# LEDs.net
KiCad netlist of a schematic drawn in Altium Designer
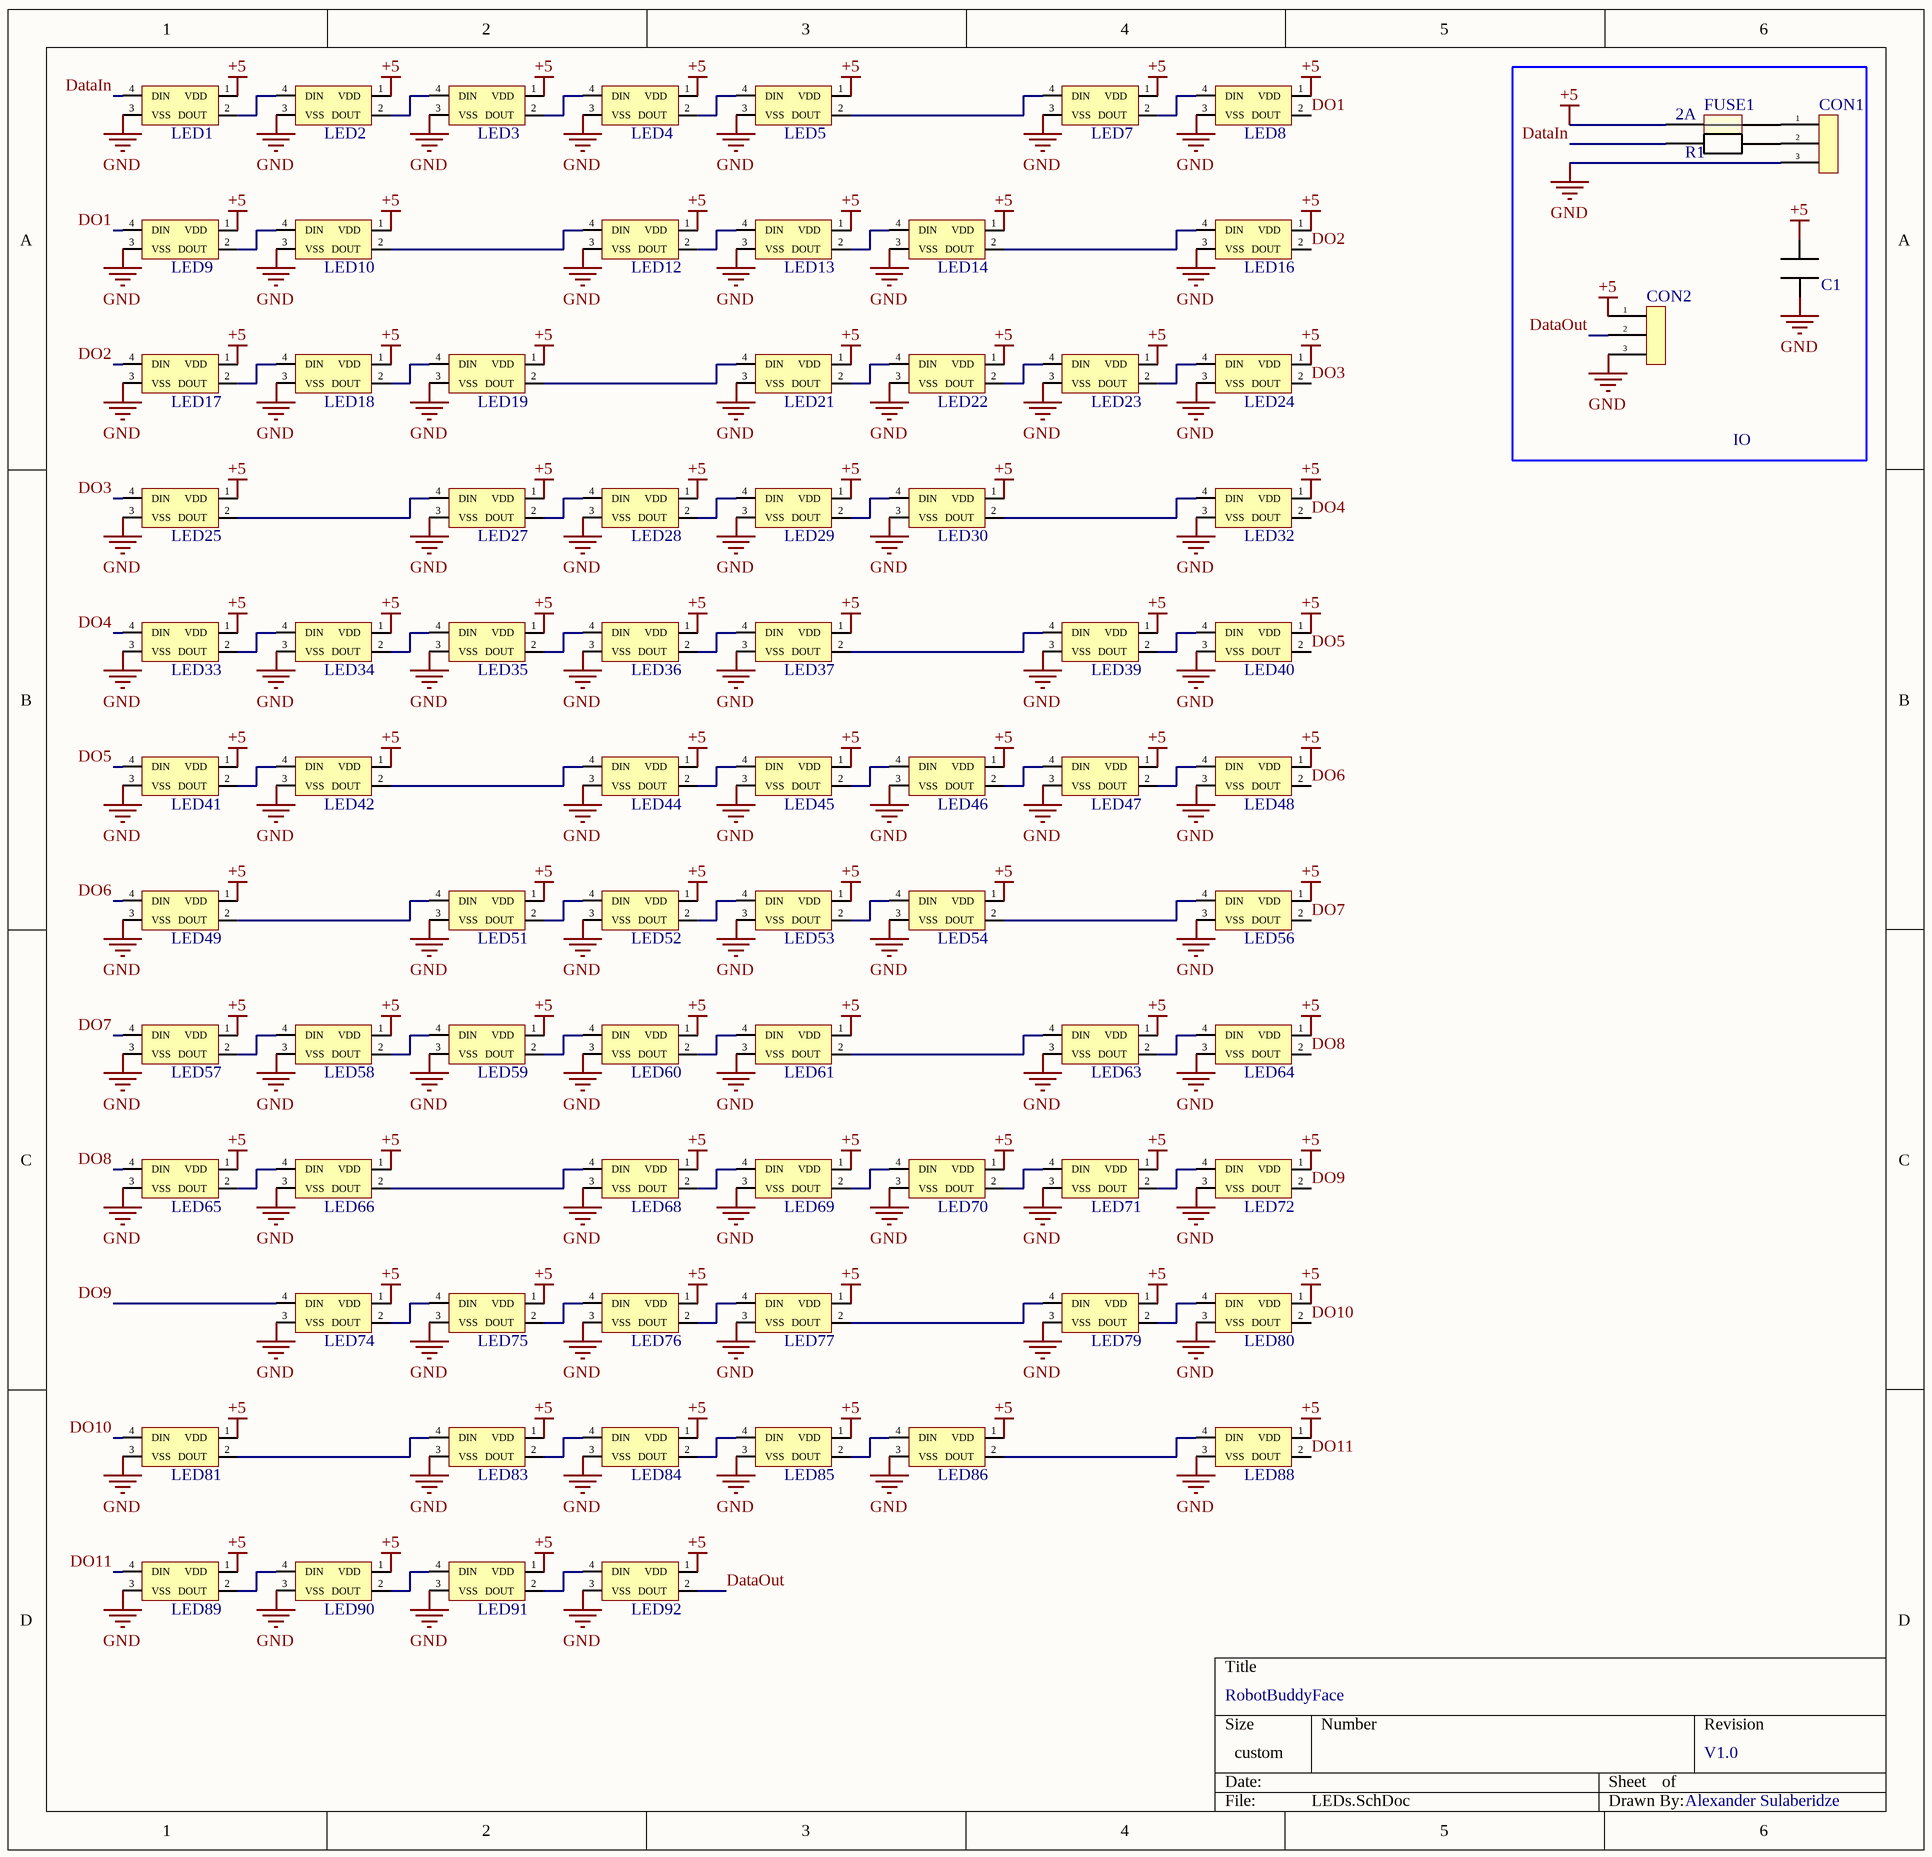
[diagram p0: LEDs.SchDoc]

(export (version "E")
  (design (tool "Eeschema 10.0.6"))
  (components
    (comp (ref "C1")
      (value "47uF 10V")
      (footprint "CAP_1206")
      (description "CAP_1206")
      (libsource (lib "Passives") (part "CAP_1206"))
    )
    (comp (ref "CON1")
      (value "HX-XH2.54-3PZZ")
      (footprint "JST XH2.54mm 1x3")
      (description "Connector Header 3 position 2.54mm Pitch 3A Through Hole -25℃~+85℃")
      (libsource (lib "Connectors") (part "JST XH2.54mm 1x3"))
    )
    (comp (ref "CON2")
      (value "HX-XH2.54-3PZZ")
      (footprint "JST XH2.54mm 1x3")
      (description "Connector Header 3 position 2.54mm Pitch 3A Through Hole -25℃~+85℃")
      (libsource (lib "Connectors") (part "JST XH2.54mm 1x3"))
    )
    (comp (ref "FUSE1")
      (value "2A")
      (footprint "FUSE_1206")
      (description "Fuse_1206")
      (libsource (lib "Passives") (part "Fuse_1206"))
    )
    (comp (ref "LED1")
      (value "Worldsemi WS2812B-B/W")
      (footprint "SMD5050 - WS2812B-B")
      (description "Intelligent control LED integrated light source")
      (libsource (lib "Passives") (part "Worldsemi WS2812B-B/W"))
    )
    (comp (ref "LED2")
      (value "Worldsemi WS2812B-B/W")
      (footprint "SMD5050 - WS2812B-B")
      (description "Intelligent control LED integrated light source")
      (libsource (lib "Passives") (part "Worldsemi WS2812B-B/W"))
    )
    (comp (ref "LED3")
      (value "Worldsemi WS2812B-B/W")
      (footprint "SMD5050 - WS2812B-B")
      (description "Intelligent control LED integrated light source")
      (libsource (lib "Passives") (part "Worldsemi WS2812B-B/W"))
    )
    (comp (ref "LED4")
      (value "Worldsemi WS2812B-B/W")
      (footprint "SMD5050 - WS2812B-B")
      (description "Intelligent control LED integrated light source")
      (libsource (lib "Passives") (part "Worldsemi WS2812B-B/W"))
    )
    (comp (ref "LED5")
      (value "Worldsemi WS2812B-B/W")
      (footprint "SMD5050 - WS2812B-B")
      (description "Intelligent control LED integrated light source")
      (libsource (lib "Passives") (part "Worldsemi WS2812B-B/W"))
    )
    (comp (ref "LED7")
      (value "Worldsemi WS2812B-B/W")
      (footprint "SMD5050 - WS2812B-B")
      (description "Intelligent control LED integrated light source")
      (libsource (lib "Passives") (part "Worldsemi WS2812B-B/W"))
    )
    (comp (ref "LED8")
      (value "Worldsemi WS2812B-B/W")
      (footprint "SMD5050 - WS2812B-B")
      (description "Intelligent control LED integrated light source")
      (libsource (lib "Passives") (part "Worldsemi WS2812B-B/W"))
    )
    (comp (ref "LED9")
      (value "Worldsemi WS2812B-B/W")
      (footprint "SMD5050 - WS2812B-B")
      (description "Intelligent control LED integrated light source")
      (libsource (lib "Passives") (part "Worldsemi WS2812B-B/W"))
    )
    (comp (ref "LED10")
      (value "Worldsemi WS2812B-B/W")
      (footprint "SMD5050 - WS2812B-B")
      (description "Intelligent control LED integrated light source")
      (libsource (lib "Passives") (part "Worldsemi WS2812B-B/W"))
    )
    (comp (ref "LED12")
      (value "Worldsemi WS2812B-B/W")
      (footprint "SMD5050 - WS2812B-B")
      (description "Intelligent control LED integrated light source")
      (libsource (lib "Passives") (part "Worldsemi WS2812B-B/W"))
    )
    (comp (ref "LED13")
      (value "Worldsemi WS2812B-B/W")
      (footprint "SMD5050 - WS2812B-B")
      (description "Intelligent control LED integrated light source")
      (libsource (lib "Passives") (part "Worldsemi WS2812B-B/W"))
    )
    (comp (ref "LED14")
      (value "Worldsemi WS2812B-B/W")
      (footprint "SMD5050 - WS2812B-B")
      (description "Intelligent control LED integrated light source")
      (libsource (lib "Passives") (part "Worldsemi WS2812B-B/W"))
    )
    (comp (ref "LED16")
      (value "Worldsemi WS2812B-B/W")
      (footprint "SMD5050 - WS2812B-B")
      (description "Intelligent control LED integrated light source")
      (libsource (lib "Passives") (part "Worldsemi WS2812B-B/W"))
    )
    (comp (ref "LED17")
      (value "Worldsemi WS2812B-B/W")
      (footprint "SMD5050 - WS2812B-B")
      (description "Intelligent control LED integrated light source")
      (libsource (lib "Passives") (part "Worldsemi WS2812B-B/W"))
    )
    (comp (ref "LED18")
      (value "Worldsemi WS2812B-B/W")
      (footprint "SMD5050 - WS2812B-B")
      (description "Intelligent control LED integrated light source")
      (libsource (lib "Passives") (part "Worldsemi WS2812B-B/W"))
    )
    (comp (ref "LED19")
      (value "Worldsemi WS2812B-B/W")
      (footprint "SMD5050 - WS2812B-B")
      (description "Intelligent control LED integrated light source")
      (libsource (lib "Passives") (part "Worldsemi WS2812B-B/W"))
    )
    (comp (ref "LED21")
      (value "Worldsemi WS2812B-B/W")
      (footprint "SMD5050 - WS2812B-B")
      (description "Intelligent control LED integrated light source")
      (libsource (lib "Passives") (part "Worldsemi WS2812B-B/W"))
    )
    (comp (ref "LED22")
      (value "Worldsemi WS2812B-B/W")
      (footprint "SMD5050 - WS2812B-B")
      (description "Intelligent control LED integrated light source")
      (libsource (lib "Passives") (part "Worldsemi WS2812B-B/W"))
    )
    (comp (ref "LED23")
      (value "Worldsemi WS2812B-B/W")
      (footprint "SMD5050 - WS2812B-B")
      (description "Intelligent control LED integrated light source")
      (libsource (lib "Passives") (part "Worldsemi WS2812B-B/W"))
    )
    (comp (ref "LED24")
      (value "Worldsemi WS2812B-B/W")
      (footprint "SMD5050 - WS2812B-B")
      (description "Intelligent control LED integrated light source")
      (libsource (lib "Passives") (part "Worldsemi WS2812B-B/W"))
    )
    (comp (ref "LED25")
      (value "Worldsemi WS2812B-B/W")
      (footprint "SMD5050 - WS2812B-B")
      (description "Intelligent control LED integrated light source")
      (libsource (lib "Passives") (part "Worldsemi WS2812B-B/W"))
    )
    (comp (ref "LED27")
      (value "Worldsemi WS2812B-B/W")
      (footprint "SMD5050 - WS2812B-B")
      (description "Intelligent control LED integrated light source")
      (libsource (lib "Passives") (part "Worldsemi WS2812B-B/W"))
    )
    (comp (ref "LED28")
      (value "Worldsemi WS2812B-B/W")
      (footprint "SMD5050 - WS2812B-B")
      (description "Intelligent control LED integrated light source")
      (libsource (lib "Passives") (part "Worldsemi WS2812B-B/W"))
    )
    (comp (ref "LED29")
      (value "Worldsemi WS2812B-B/W")
      (footprint "SMD5050 - WS2812B-B")
      (description "Intelligent control LED integrated light source")
      (libsource (lib "Passives") (part "Worldsemi WS2812B-B/W"))
    )
    (comp (ref "LED30")
      (value "Worldsemi WS2812B-B/W")
      (footprint "SMD5050 - WS2812B-B")
      (description "Intelligent control LED integrated light source")
      (libsource (lib "Passives") (part "Worldsemi WS2812B-B/W"))
    )
    (comp (ref "LED32")
      (value "Worldsemi WS2812B-B/W")
      (footprint "SMD5050 - WS2812B-B")
      (description "Intelligent control LED integrated light source")
      (libsource (lib "Passives") (part "Worldsemi WS2812B-B/W"))
    )
    (comp (ref "LED33")
      (value "Worldsemi WS2812B-B/W")
      (footprint "SMD5050 - WS2812B-B")
      (description "Intelligent control LED integrated light source")
      (libsource (lib "Passives") (part "Worldsemi WS2812B-B/W"))
    )
    (comp (ref "LED34")
      (value "Worldsemi WS2812B-B/W")
      (footprint "SMD5050 - WS2812B-B")
      (description "Intelligent control LED integrated light source")
      (libsource (lib "Passives") (part "Worldsemi WS2812B-B/W"))
    )
    (comp (ref "LED35")
      (value "Worldsemi WS2812B-B/W")
      (footprint "SMD5050 - WS2812B-B")
      (description "Intelligent control LED integrated light source")
      (libsource (lib "Passives") (part "Worldsemi WS2812B-B/W"))
    )
    (comp (ref "LED36")
      (value "Worldsemi WS2812B-B/W")
      (footprint "SMD5050 - WS2812B-B")
      (description "Intelligent control LED integrated light source")
      (libsource (lib "Passives") (part "Worldsemi WS2812B-B/W"))
    )
    (comp (ref "LED37")
      (value "Worldsemi WS2812B-B/W")
      (footprint "SMD5050 - WS2812B-B")
      (description "Intelligent control LED integrated light source")
      (libsource (lib "Passives") (part "Worldsemi WS2812B-B/W"))
    )
    (comp (ref "LED39")
      (value "Worldsemi WS2812B-B/W")
      (footprint "SMD5050 - WS2812B-B")
      (description "Intelligent control LED integrated light source")
      (libsource (lib "Passives") (part "Worldsemi WS2812B-B/W"))
    )
    (comp (ref "LED40")
      (value "Worldsemi WS2812B-B/W")
      (footprint "SMD5050 - WS2812B-B")
      (description "Intelligent control LED integrated light source")
      (libsource (lib "Passives") (part "Worldsemi WS2812B-B/W"))
    )
    (comp (ref "LED41")
      (value "Worldsemi WS2812B-B/W")
      (footprint "SMD5050 - WS2812B-B")
      (description "Intelligent control LED integrated light source")
      (libsource (lib "Passives") (part "Worldsemi WS2812B-B/W"))
    )
    (comp (ref "LED42")
      (value "Worldsemi WS2812B-B/W")
      (footprint "SMD5050 - WS2812B-B")
      (description "Intelligent control LED integrated light source")
      (libsource (lib "Passives") (part "Worldsemi WS2812B-B/W"))
    )
    (comp (ref "LED44")
      (value "Worldsemi WS2812B-B/W")
      (footprint "SMD5050 - WS2812B-B")
      (description "Intelligent control LED integrated light source")
      (libsource (lib "Passives") (part "Worldsemi WS2812B-B/W"))
    )
    (comp (ref "LED45")
      (value "Worldsemi WS2812B-B/W")
      (footprint "SMD5050 - WS2812B-B")
      (description "Intelligent control LED integrated light source")
      (libsource (lib "Passives") (part "Worldsemi WS2812B-B/W"))
    )
    (comp (ref "LED46")
      (value "Worldsemi WS2812B-B/W")
      (footprint "SMD5050 - WS2812B-B")
      (description "Intelligent control LED integrated light source")
      (libsource (lib "Passives") (part "Worldsemi WS2812B-B/W"))
    )
    (comp (ref "LED47")
      (value "Worldsemi WS2812B-B/W")
      (footprint "SMD5050 - WS2812B-B")
      (description "Intelligent control LED integrated light source")
      (libsource (lib "Passives") (part "Worldsemi WS2812B-B/W"))
    )
    (comp (ref "LED48")
      (value "Worldsemi WS2812B-B/W")
      (footprint "SMD5050 - WS2812B-B")
      (description "Intelligent control LED integrated light source")
      (libsource (lib "Passives") (part "Worldsemi WS2812B-B/W"))
    )
    (comp (ref "LED49")
      (value "Worldsemi WS2812B-B/W")
      (footprint "SMD5050 - WS2812B-B")
      (description "Intelligent control LED integrated light source")
      (libsource (lib "Passives") (part "Worldsemi WS2812B-B/W"))
    )
    (comp (ref "LED51")
      (value "Worldsemi WS2812B-B/W")
      (footprint "SMD5050 - WS2812B-B")
      (description "Intelligent control LED integrated light source")
      (libsource (lib "Passives") (part "Worldsemi WS2812B-B/W"))
    )
    (comp (ref "LED52")
      (value "Worldsemi WS2812B-B/W")
      (footprint "SMD5050 - WS2812B-B")
      (description "Intelligent control LED integrated light source")
      (libsource (lib "Passives") (part "Worldsemi WS2812B-B/W"))
    )
    (comp (ref "LED53")
      (value "Worldsemi WS2812B-B/W")
      (footprint "SMD5050 - WS2812B-B")
      (description "Intelligent control LED integrated light source")
      (libsource (lib "Passives") (part "Worldsemi WS2812B-B/W"))
    )
    (comp (ref "LED54")
      (value "Worldsemi WS2812B-B/W")
      (footprint "SMD5050 - WS2812B-B")
      (description "Intelligent control LED integrated light source")
      (libsource (lib "Passives") (part "Worldsemi WS2812B-B/W"))
    )
    (comp (ref "LED56")
      (value "Worldsemi WS2812B-B/W")
      (footprint "SMD5050 - WS2812B-B")
      (description "Intelligent control LED integrated light source")
      (libsource (lib "Passives") (part "Worldsemi WS2812B-B/W"))
    )
    (comp (ref "LED57")
      (value "Worldsemi WS2812B-B/W")
      (footprint "SMD5050 - WS2812B-B")
      (description "Intelligent control LED integrated light source")
      (libsource (lib "Passives") (part "Worldsemi WS2812B-B/W"))
    )
    (comp (ref "LED58")
      (value "Worldsemi WS2812B-B/W")
      (footprint "SMD5050 - WS2812B-B")
      (description "Intelligent control LED integrated light source")
      (libsource (lib "Passives") (part "Worldsemi WS2812B-B/W"))
    )
    (comp (ref "LED59")
      (value "Worldsemi WS2812B-B/W")
      (footprint "SMD5050 - WS2812B-B")
      (description "Intelligent control LED integrated light source")
      (libsource (lib "Passives") (part "Worldsemi WS2812B-B/W"))
    )
    (comp (ref "LED60")
      (value "Worldsemi WS2812B-B/W")
      (footprint "SMD5050 - WS2812B-B")
      (description "Intelligent control LED integrated light source")
      (libsource (lib "Passives") (part "Worldsemi WS2812B-B/W"))
    )
    (comp (ref "LED61")
      (value "Worldsemi WS2812B-B/W")
      (footprint "SMD5050 - WS2812B-B")
      (description "Intelligent control LED integrated light source")
      (libsource (lib "Passives") (part "Worldsemi WS2812B-B/W"))
    )
    (comp (ref "LED63")
      (value "Worldsemi WS2812B-B/W")
      (footprint "SMD5050 - WS2812B-B")
      (description "Intelligent control LED integrated light source")
      (libsource (lib "Passives") (part "Worldsemi WS2812B-B/W"))
    )
    (comp (ref "LED64")
      (value "Worldsemi WS2812B-B/W")
      (footprint "SMD5050 - WS2812B-B")
      (description "Intelligent control LED integrated light source")
      (libsource (lib "Passives") (part "Worldsemi WS2812B-B/W"))
    )
    (comp (ref "LED65")
      (value "Worldsemi WS2812B-B/W")
      (footprint "SMD5050 - WS2812B-B")
      (description "Intelligent control LED integrated light source")
      (libsource (lib "Passives") (part "Worldsemi WS2812B-B/W"))
    )
    (comp (ref "LED66")
      (value "Worldsemi WS2812B-B/W")
      (footprint "SMD5050 - WS2812B-B")
      (description "Intelligent control LED integrated light source")
      (libsource (lib "Passives") (part "Worldsemi WS2812B-B/W"))
    )
    (comp (ref "LED68")
      (value "Worldsemi WS2812B-B/W")
      (footprint "SMD5050 - WS2812B-B")
      (description "Intelligent control LED integrated light source")
      (libsource (lib "Passives") (part "Worldsemi WS2812B-B/W"))
    )
    (comp (ref "LED69")
      (value "Worldsemi WS2812B-B/W")
      (footprint "SMD5050 - WS2812B-B")
      (description "Intelligent control LED integrated light source")
      (libsource (lib "Passives") (part "Worldsemi WS2812B-B/W"))
    )
    (comp (ref "LED70")
      (value "Worldsemi WS2812B-B/W")
      (footprint "SMD5050 - WS2812B-B")
      (description "Intelligent control LED integrated light source")
      (libsource (lib "Passives") (part "Worldsemi WS2812B-B/W"))
    )
    (comp (ref "LED71")
      (value "Worldsemi WS2812B-B/W")
      (footprint "SMD5050 - WS2812B-B")
      (description "Intelligent control LED integrated light source")
      (libsource (lib "Passives") (part "Worldsemi WS2812B-B/W"))
    )
    (comp (ref "LED72")
      (value "Worldsemi WS2812B-B/W")
      (footprint "SMD5050 - WS2812B-B")
      (description "Intelligent control LED integrated light source")
      (libsource (lib "Passives") (part "Worldsemi WS2812B-B/W"))
    )
    (comp (ref "LED74")
      (value "Worldsemi WS2812B-B/W")
      (footprint "SMD5050 - WS2812B-B")
      (description "Intelligent control LED integrated light source")
      (libsource (lib "Passives") (part "Worldsemi WS2812B-B/W"))
    )
    (comp (ref "LED75")
      (value "Worldsemi WS2812B-B/W")
      (footprint "SMD5050 - WS2812B-B")
      (description "Intelligent control LED integrated light source")
      (libsource (lib "Passives") (part "Worldsemi WS2812B-B/W"))
    )
    (comp (ref "LED76")
      (value "Worldsemi WS2812B-B/W")
      (footprint "SMD5050 - WS2812B-B")
      (description "Intelligent control LED integrated light source")
      (libsource (lib "Passives") (part "Worldsemi WS2812B-B/W"))
    )
    (comp (ref "LED77")
      (value "Worldsemi WS2812B-B/W")
      (footprint "SMD5050 - WS2812B-B")
      (description "Intelligent control LED integrated light source")
      (libsource (lib "Passives") (part "Worldsemi WS2812B-B/W"))
    )
    (comp (ref "LED79")
      (value "Worldsemi WS2812B-B/W")
      (footprint "SMD5050 - WS2812B-B")
      (description "Intelligent control LED integrated light source")
      (libsource (lib "Passives") (part "Worldsemi WS2812B-B/W"))
    )
    (comp (ref "LED80")
      (value "Worldsemi WS2812B-B/W")
      (footprint "SMD5050 - WS2812B-B")
      (description "Intelligent control LED integrated light source")
      (libsource (lib "Passives") (part "Worldsemi WS2812B-B/W"))
    )
    (comp (ref "LED81")
      (value "Worldsemi WS2812B-B/W")
      (footprint "SMD5050 - WS2812B-B")
      (description "Intelligent control LED integrated light source")
      (libsource (lib "Passives") (part "Worldsemi WS2812B-B/W"))
    )
    (comp (ref "LED83")
      (value "Worldsemi WS2812B-B/W")
      (footprint "SMD5050 - WS2812B-B")
      (description "Intelligent control LED integrated light source")
      (libsource (lib "Passives") (part "Worldsemi WS2812B-B/W"))
    )
    (comp (ref "LED84")
      (value "Worldsemi WS2812B-B/W")
      (footprint "SMD5050 - WS2812B-B")
      (description "Intelligent control LED integrated light source")
      (libsource (lib "Passives") (part "Worldsemi WS2812B-B/W"))
    )
    (comp (ref "LED85")
      (value "Worldsemi WS2812B-B/W")
      (footprint "SMD5050 - WS2812B-B")
      (description "Intelligent control LED integrated light source")
      (libsource (lib "Passives") (part "Worldsemi WS2812B-B/W"))
    )
    (comp (ref "LED86")
      (value "Worldsemi WS2812B-B/W")
      (footprint "SMD5050 - WS2812B-B")
      (description "Intelligent control LED integrated light source")
      (libsource (lib "Passives") (part "Worldsemi WS2812B-B/W"))
    )
    (comp (ref "LED88")
      (value "Worldsemi WS2812B-B/W")
      (footprint "SMD5050 - WS2812B-B")
      (description "Intelligent control LED integrated light source")
      (libsource (lib "Passives") (part "Worldsemi WS2812B-B/W"))
    )
    (comp (ref "LED89")
      (value "Worldsemi WS2812B-B/W")
      (footprint "SMD5050 - WS2812B-B")
      (description "Intelligent control LED integrated light source")
      (libsource (lib "Passives") (part "Worldsemi WS2812B-B/W"))
    )
    (comp (ref "LED90")
      (value "Worldsemi WS2812B-B/W")
      (footprint "SMD5050 - WS2812B-B")
      (description "Intelligent control LED integrated light source")
      (libsource (lib "Passives") (part "Worldsemi WS2812B-B/W"))
    )
    (comp (ref "LED91")
      (value "Worldsemi WS2812B-B/W")
      (footprint "SMD5050 - WS2812B-B")
      (description "Intelligent control LED integrated light source")
      (libsource (lib "Passives") (part "Worldsemi WS2812B-B/W"))
    )
    (comp (ref "LED92")
      (value "Worldsemi WS2812B-B/W")
      (footprint "SMD5050 - WS2812B-B")
      (description "Intelligent control LED integrated light source")
      (libsource (lib "Passives") (part "Worldsemi WS2812B-B/W"))
    )
    (comp (ref "R1")
      (value "500")
      (footprint "RES_0805")
      (description "RES_0805")
      (libsource (lib "Passives") (part "RES_0805"))
    )
  )
  (nets
    (net (code "1") (name "+5") (class "Default")
      (node (ref "C1") (pin "2") (pinfunction "2_2") (pintype "passive"))
      (node (ref "CON2") (pin "1") (pinfunction "1_1") (pintype "passive"))
      (node (ref "FUSE1") (pin "1") (pinfunction "1_1") (pintype "passive"))
      (node (ref "LED1") (pin "1") (pinfunction "VDD_1") (pintype "passive"))
      (node (ref "LED10") (pin "1") (pinfunction "VDD_1") (pintype "passive"))
      (node (ref "LED12") (pin "1") (pinfunction "VDD_1") (pintype "passive"))
      (node (ref "LED13") (pin "1") (pinfunction "VDD_1") (pintype "passive"))
      (node (ref "LED14") (pin "1") (pinfunction "VDD_1") (pintype "passive"))
      (node (ref "LED16") (pin "1") (pinfunction "VDD_1") (pintype "passive"))
      (node (ref "LED17") (pin "1") (pinfunction "VDD_1") (pintype "passive"))
      (node (ref "LED18") (pin "1") (pinfunction "VDD_1") (pintype "passive"))
      (node (ref "LED19") (pin "1") (pinfunction "VDD_1") (pintype "passive"))
      (node (ref "LED2") (pin "1") (pinfunction "VDD_1") (pintype "passive"))
      (node (ref "LED21") (pin "1") (pinfunction "VDD_1") (pintype "passive"))
      (node (ref "LED22") (pin "1") (pinfunction "VDD_1") (pintype "passive"))
      (node (ref "LED23") (pin "1") (pinfunction "VDD_1") (pintype "passive"))
      (node (ref "LED24") (pin "1") (pinfunction "VDD_1") (pintype "passive"))
      (node (ref "LED25") (pin "1") (pinfunction "VDD_1") (pintype "passive"))
      (node (ref "LED27") (pin "1") (pinfunction "VDD_1") (pintype "passive"))
      (node (ref "LED28") (pin "1") (pinfunction "VDD_1") (pintype "passive"))
      (node (ref "LED29") (pin "1") (pinfunction "VDD_1") (pintype "passive"))
      (node (ref "LED3") (pin "1") (pinfunction "VDD_1") (pintype "passive"))
      (node (ref "LED30") (pin "1") (pinfunction "VDD_1") (pintype "passive"))
      (node (ref "LED32") (pin "1") (pinfunction "VDD_1") (pintype "passive"))
      (node (ref "LED33") (pin "1") (pinfunction "VDD_1") (pintype "passive"))
      (node (ref "LED34") (pin "1") (pinfunction "VDD_1") (pintype "passive"))
      (node (ref "LED35") (pin "1") (pinfunction "VDD_1") (pintype "passive"))
      (node (ref "LED36") (pin "1") (pinfunction "VDD_1") (pintype "passive"))
      (node (ref "LED37") (pin "1") (pinfunction "VDD_1") (pintype "passive"))
      (node (ref "LED39") (pin "1") (pinfunction "VDD_1") (pintype "passive"))
      (node (ref "LED4") (pin "1") (pinfunction "VDD_1") (pintype "passive"))
      (node (ref "LED40") (pin "1") (pinfunction "VDD_1") (pintype "passive"))
      (node (ref "LED41") (pin "1") (pinfunction "VDD_1") (pintype "passive"))
      (node (ref "LED42") (pin "1") (pinfunction "VDD_1") (pintype "passive"))
      (node (ref "LED44") (pin "1") (pinfunction "VDD_1") (pintype "passive"))
      (node (ref "LED45") (pin "1") (pinfunction "VDD_1") (pintype "passive"))
      (node (ref "LED46") (pin "1") (pinfunction "VDD_1") (pintype "passive"))
      (node (ref "LED47") (pin "1") (pinfunction "VDD_1") (pintype "passive"))
      (node (ref "LED48") (pin "1") (pinfunction "VDD_1") (pintype "passive"))
      (node (ref "LED49") (pin "1") (pinfunction "VDD_1") (pintype "passive"))
      (node (ref "LED5") (pin "1") (pinfunction "VDD_1") (pintype "passive"))
      (node (ref "LED51") (pin "1") (pinfunction "VDD_1") (pintype "passive"))
      (node (ref "LED52") (pin "1") (pinfunction "VDD_1") (pintype "passive"))
      (node (ref "LED53") (pin "1") (pinfunction "VDD_1") (pintype "passive"))
      (node (ref "LED54") (pin "1") (pinfunction "VDD_1") (pintype "passive"))
      (node (ref "LED56") (pin "1") (pinfunction "VDD_1") (pintype "passive"))
      (node (ref "LED57") (pin "1") (pinfunction "VDD_1") (pintype "passive"))
      (node (ref "LED58") (pin "1") (pinfunction "VDD_1") (pintype "passive"))
      (node (ref "LED59") (pin "1") (pinfunction "VDD_1") (pintype "passive"))
      (node (ref "LED60") (pin "1") (pinfunction "VDD_1") (pintype "passive"))
      (node (ref "LED61") (pin "1") (pinfunction "VDD_1") (pintype "passive"))
      (node (ref "LED63") (pin "1") (pinfunction "VDD_1") (pintype "passive"))
      (node (ref "LED64") (pin "1") (pinfunction "VDD_1") (pintype "passive"))
      (node (ref "LED65") (pin "1") (pinfunction "VDD_1") (pintype "passive"))
      (node (ref "LED66") (pin "1") (pinfunction "VDD_1") (pintype "passive"))
      (node (ref "LED68") (pin "1") (pinfunction "VDD_1") (pintype "passive"))
      (node (ref "LED69") (pin "1") (pinfunction "VDD_1") (pintype "passive"))
      (node (ref "LED7") (pin "1") (pinfunction "VDD_1") (pintype "passive"))
      (node (ref "LED70") (pin "1") (pinfunction "VDD_1") (pintype "passive"))
      (node (ref "LED71") (pin "1") (pinfunction "VDD_1") (pintype "passive"))
      (node (ref "LED72") (pin "1") (pinfunction "VDD_1") (pintype "passive"))
      (node (ref "LED74") (pin "1") (pinfunction "VDD_1") (pintype "passive"))
      (node (ref "LED75") (pin "1") (pinfunction "VDD_1") (pintype "passive"))
      (node (ref "LED76") (pin "1") (pinfunction "VDD_1") (pintype "passive"))
      (node (ref "LED77") (pin "1") (pinfunction "VDD_1") (pintype "passive"))
      (node (ref "LED79") (pin "1") (pinfunction "VDD_1") (pintype "passive"))
      (node (ref "LED8") (pin "1") (pinfunction "VDD_1") (pintype "passive"))
      (node (ref "LED80") (pin "1") (pinfunction "VDD_1") (pintype "passive"))
      (node (ref "LED81") (pin "1") (pinfunction "VDD_1") (pintype "passive"))
      (node (ref "LED83") (pin "1") (pinfunction "VDD_1") (pintype "passive"))
      (node (ref "LED84") (pin "1") (pinfunction "VDD_1") (pintype "passive"))
      (node (ref "LED85") (pin "1") (pinfunction "VDD_1") (pintype "passive"))
      (node (ref "LED86") (pin "1") (pinfunction "VDD_1") (pintype "passive"))
      (node (ref "LED88") (pin "1") (pinfunction "VDD_1") (pintype "passive"))
      (node (ref "LED89") (pin "1") (pinfunction "VDD_1") (pintype "passive"))
      (node (ref "LED9") (pin "1") (pinfunction "VDD_1") (pintype "passive"))
      (node (ref "LED90") (pin "1") (pinfunction "VDD_1") (pintype "passive"))
      (node (ref "LED91") (pin "1") (pinfunction "VDD_1") (pintype "passive"))
      (node (ref "LED92") (pin "1") (pinfunction "VDD_1") (pintype "passive"))
    )
    (net (code "2") (name "/DO1") (class "Default")
      (node (ref "LED8") (pin "2") (pinfunction "DOUT_2") (pintype "passive"))
      (node (ref "LED9") (pin "4") (pinfunction "DIN_4") (pintype "passive"))
    )
    (net (code "3") (name "/DO2") (class "Default")
      (node (ref "LED16") (pin "2") (pinfunction "DOUT_2") (pintype "passive"))
      (node (ref "LED17") (pin "4") (pinfunction "DIN_4") (pintype "passive"))
    )
    (net (code "4") (name "/DO3") (class "Default")
      (node (ref "LED24") (pin "2") (pinfunction "DOUT_2") (pintype "passive"))
      (node (ref "LED25") (pin "4") (pinfunction "DIN_4") (pintype "passive"))
    )
    (net (code "5") (name "/DO4") (class "Default")
      (node (ref "LED32") (pin "2") (pinfunction "DOUT_2") (pintype "passive"))
      (node (ref "LED33") (pin "4") (pinfunction "DIN_4") (pintype "passive"))
    )
    (net (code "6") (name "/DO5") (class "Default")
      (node (ref "LED40") (pin "2") (pinfunction "DOUT_2") (pintype "passive"))
      (node (ref "LED41") (pin "4") (pinfunction "DIN_4") (pintype "passive"))
    )
    (net (code "7") (name "/DO6") (class "Default")
      (node (ref "LED48") (pin "2") (pinfunction "DOUT_2") (pintype "passive"))
      (node (ref "LED49") (pin "4") (pinfunction "DIN_4") (pintype "passive"))
    )
    (net (code "8") (name "/DO7") (class "Default")
      (node (ref "LED56") (pin "2") (pinfunction "DOUT_2") (pintype "passive"))
      (node (ref "LED57") (pin "4") (pinfunction "DIN_4") (pintype "passive"))
    )
    (net (code "9") (name "/DO8") (class "Default")
      (node (ref "LED64") (pin "2") (pinfunction "DOUT_2") (pintype "passive"))
      (node (ref "LED65") (pin "4") (pinfunction "DIN_4") (pintype "passive"))
    )
    (net (code "10") (name "/DO9") (class "Default")
      (node (ref "LED72") (pin "2") (pinfunction "DOUT_2") (pintype "passive"))
      (node (ref "LED74") (pin "4") (pinfunction "DIN_4") (pintype "passive"))
    )
    (net (code "11") (name "/DO10") (class "Default")
      (node (ref "LED80") (pin "2") (pinfunction "DOUT_2") (pintype "passive"))
      (node (ref "LED81") (pin "4") (pinfunction "DIN_4") (pintype "passive"))
    )
    (net (code "12") (name "/DO11") (class "Default")
      (node (ref "LED88") (pin "2") (pinfunction "DOUT_2") (pintype "passive"))
      (node (ref "LED89") (pin "4") (pinfunction "DIN_4") (pintype "passive"))
    )
    (net (code "13") (name "/DataIn") (class "Default")
      (node (ref "LED1") (pin "4") (pinfunction "DIN_4") (pintype "passive"))
      (node (ref "R1") (pin "1") (pinfunction "1_1") (pintype "passive"))
    )
    (net (code "14") (name "/DataOut") (class "Default")
      (node (ref "CON2") (pin "2") (pinfunction "2_2") (pintype "passive"))
      (node (ref "LED92") (pin "2") (pinfunction "DOUT_2") (pintype "passive"))
    )
    (net (code "15") (name "GND") (class "Default")
      (node (ref "C1") (pin "1") (pinfunction "1_1") (pintype "passive"))
      (node (ref "CON1") (pin "3") (pinfunction "3_3") (pintype "passive"))
      (node (ref "CON2") (pin "3") (pinfunction "3_3") (pintype "passive"))
      (node (ref "LED1") (pin "3") (pinfunction "VSS_3") (pintype "passive"))
      (node (ref "LED10") (pin "3") (pinfunction "VSS_3") (pintype "passive"))
      (node (ref "LED12") (pin "3") (pinfunction "VSS_3") (pintype "passive"))
      (node (ref "LED13") (pin "3") (pinfunction "VSS_3") (pintype "passive"))
      (node (ref "LED14") (pin "3") (pinfunction "VSS_3") (pintype "passive"))
      (node (ref "LED16") (pin "3") (pinfunction "VSS_3") (pintype "passive"))
      (node (ref "LED17") (pin "3") (pinfunction "VSS_3") (pintype "passive"))
      (node (ref "LED18") (pin "3") (pinfunction "VSS_3") (pintype "passive"))
      (node (ref "LED19") (pin "3") (pinfunction "VSS_3") (pintype "passive"))
      (node (ref "LED2") (pin "3") (pinfunction "VSS_3") (pintype "passive"))
      (node (ref "LED21") (pin "3") (pinfunction "VSS_3") (pintype "passive"))
      (node (ref "LED22") (pin "3") (pinfunction "VSS_3") (pintype "passive"))
      (node (ref "LED23") (pin "3") (pinfunction "VSS_3") (pintype "passive"))
      (node (ref "LED24") (pin "3") (pinfunction "VSS_3") (pintype "passive"))
      (node (ref "LED25") (pin "3") (pinfunction "VSS_3") (pintype "passive"))
      (node (ref "LED27") (pin "3") (pinfunction "VSS_3") (pintype "passive"))
      (node (ref "LED28") (pin "3") (pinfunction "VSS_3") (pintype "passive"))
      (node (ref "LED29") (pin "3") (pinfunction "VSS_3") (pintype "passive"))
      (node (ref "LED3") (pin "3") (pinfunction "VSS_3") (pintype "passive"))
      (node (ref "LED30") (pin "3") (pinfunction "VSS_3") (pintype "passive"))
      (node (ref "LED32") (pin "3") (pinfunction "VSS_3") (pintype "passive"))
      (node (ref "LED33") (pin "3") (pinfunction "VSS_3") (pintype "passive"))
      (node (ref "LED34") (pin "3") (pinfunction "VSS_3") (pintype "passive"))
      (node (ref "LED35") (pin "3") (pinfunction "VSS_3") (pintype "passive"))
      (node (ref "LED36") (pin "3") (pinfunction "VSS_3") (pintype "passive"))
      (node (ref "LED37") (pin "3") (pinfunction "VSS_3") (pintype "passive"))
      (node (ref "LED39") (pin "3") (pinfunction "VSS_3") (pintype "passive"))
      (node (ref "LED4") (pin "3") (pinfunction "VSS_3") (pintype "passive"))
      (node (ref "LED40") (pin "3") (pinfunction "VSS_3") (pintype "passive"))
      (node (ref "LED41") (pin "3") (pinfunction "VSS_3") (pintype "passive"))
      (node (ref "LED42") (pin "3") (pinfunction "VSS_3") (pintype "passive"))
      (node (ref "LED44") (pin "3") (pinfunction "VSS_3") (pintype "passive"))
      (node (ref "LED45") (pin "3") (pinfunction "VSS_3") (pintype "passive"))
      (node (ref "LED46") (pin "3") (pinfunction "VSS_3") (pintype "passive"))
      (node (ref "LED47") (pin "3") (pinfunction "VSS_3") (pintype "passive"))
      (node (ref "LED48") (pin "3") (pinfunction "VSS_3") (pintype "passive"))
      (node (ref "LED49") (pin "3") (pinfunction "VSS_3") (pintype "passive"))
      (node (ref "LED5") (pin "3") (pinfunction "VSS_3") (pintype "passive"))
      (node (ref "LED51") (pin "3") (pinfunction "VSS_3") (pintype "passive"))
      (node (ref "LED52") (pin "3") (pinfunction "VSS_3") (pintype "passive"))
      (node (ref "LED53") (pin "3") (pinfunction "VSS_3") (pintype "passive"))
      (node (ref "LED54") (pin "3") (pinfunction "VSS_3") (pintype "passive"))
      (node (ref "LED56") (pin "3") (pinfunction "VSS_3") (pintype "passive"))
      (node (ref "LED57") (pin "3") (pinfunction "VSS_3") (pintype "passive"))
      (node (ref "LED58") (pin "3") (pinfunction "VSS_3") (pintype "passive"))
      (node (ref "LED59") (pin "3") (pinfunction "VSS_3") (pintype "passive"))
      (node (ref "LED60") (pin "3") (pinfunction "VSS_3") (pintype "passive"))
      (node (ref "LED61") (pin "3") (pinfunction "VSS_3") (pintype "passive"))
      (node (ref "LED63") (pin "3") (pinfunction "VSS_3") (pintype "passive"))
      (node (ref "LED64") (pin "3") (pinfunction "VSS_3") (pintype "passive"))
      (node (ref "LED65") (pin "3") (pinfunction "VSS_3") (pintype "passive"))
      (node (ref "LED66") (pin "3") (pinfunction "VSS_3") (pintype "passive"))
      (node (ref "LED68") (pin "3") (pinfunction "VSS_3") (pintype "passive"))
      (node (ref "LED69") (pin "3") (pinfunction "VSS_3") (pintype "passive"))
      (node (ref "LED7") (pin "3") (pinfunction "VSS_3") (pintype "passive"))
      (node (ref "LED70") (pin "3") (pinfunction "VSS_3") (pintype "passive"))
      (node (ref "LED71") (pin "3") (pinfunction "VSS_3") (pintype "passive"))
      (node (ref "LED72") (pin "3") (pinfunction "VSS_3") (pintype "passive"))
      (node (ref "LED74") (pin "3") (pinfunction "VSS_3") (pintype "passive"))
      (node (ref "LED75") (pin "3") (pinfunction "VSS_3") (pintype "passive"))
      (node (ref "LED76") (pin "3") (pinfunction "VSS_3") (pintype "passive"))
      (node (ref "LED77") (pin "3") (pinfunction "VSS_3") (pintype "passive"))
      (node (ref "LED79") (pin "3") (pinfunction "VSS_3") (pintype "passive"))
      (node (ref "LED8") (pin "3") (pinfunction "VSS_3") (pintype "passive"))
      (node (ref "LED80") (pin "3") (pinfunction "VSS_3") (pintype "passive"))
      (node (ref "LED81") (pin "3") (pinfunction "VSS_3") (pintype "passive"))
      (node (ref "LED83") (pin "3") (pinfunction "VSS_3") (pintype "passive"))
      (node (ref "LED84") (pin "3") (pinfunction "VSS_3") (pintype "passive"))
      (node (ref "LED85") (pin "3") (pinfunction "VSS_3") (pintype "passive"))
      (node (ref "LED86") (pin "3") (pinfunction "VSS_3") (pintype "passive"))
      (node (ref "LED88") (pin "3") (pinfunction "VSS_3") (pintype "passive"))
      (node (ref "LED89") (pin "3") (pinfunction "VSS_3") (pintype "passive"))
      (node (ref "LED9") (pin "3") (pinfunction "VSS_3") (pintype "passive"))
      (node (ref "LED90") (pin "3") (pinfunction "VSS_3") (pintype "passive"))
      (node (ref "LED91") (pin "3") (pinfunction "VSS_3") (pintype "passive"))
      (node (ref "LED92") (pin "3") (pinfunction "VSS_3") (pintype "passive"))
    )
    (net (code "16") (name "Net-(CON1-Pad1)") (class "Default")
      (node (ref "CON1") (pin "1") (pinfunction "1_1") (pintype "passive"))
      (node (ref "FUSE1") (pin "2") (pinfunction "2_2") (pintype "passive"))
    )
    (net (code "17") (name "Net-(CON1-Pad2)") (class "Default")
      (node (ref "CON1") (pin "2") (pinfunction "2_2") (pintype "passive"))
      (node (ref "R1") (pin "2") (pinfunction "2_2") (pintype "passive"))
    )
    (net (code "18") (name "Net-(LED1-DOUT)") (class "Default")
      (node (ref "LED1") (pin "2") (pinfunction "DOUT_2") (pintype "passive"))
      (node (ref "LED2") (pin "4") (pinfunction "DIN_4") (pintype "passive"))
    )
    (net (code "19") (name "Net-(LED2-DOUT)") (class "Default")
      (node (ref "LED2") (pin "2") (pinfunction "DOUT_2") (pintype "passive"))
      (node (ref "LED3") (pin "4") (pinfunction "DIN_4") (pintype "passive"))
    )
    (net (code "20") (name "Net-(LED3-DOUT)") (class "Default")
      (node (ref "LED3") (pin "2") (pinfunction "DOUT_2") (pintype "passive"))
      (node (ref "LED4") (pin "4") (pinfunction "DIN_4") (pintype "passive"))
    )
    (net (code "21") (name "Net-(LED4-DOUT)") (class "Default")
      (node (ref "LED4") (pin "2") (pinfunction "DOUT_2") (pintype "passive"))
      (node (ref "LED5") (pin "4") (pinfunction "DIN_4") (pintype "passive"))
    )
    (net (code "22") (name "Net-(LED5-DOUT)") (class "Default")
      (node (ref "LED5") (pin "2") (pinfunction "DOUT_2") (pintype "passive"))
      (node (ref "LED7") (pin "4") (pinfunction "DIN_4") (pintype "passive"))
    )
    (net (code "23") (name "Net-(LED7-DOUT)") (class "Default")
      (node (ref "LED7") (pin "2") (pinfunction "DOUT_2") (pintype "passive"))
      (node (ref "LED8") (pin "4") (pinfunction "DIN_4") (pintype "passive"))
    )
    (net (code "24") (name "Net-(LED10-DIN)") (class "Default")
      (node (ref "LED10") (pin "4") (pinfunction "DIN_4") (pintype "passive"))
      (node (ref "LED9") (pin "2") (pinfunction "DOUT_2") (pintype "passive"))
    )
    (net (code "25") (name "Net-(LED10-DOUT)") (class "Default")
      (node (ref "LED10") (pin "2") (pinfunction "DOUT_2") (pintype "passive"))
      (node (ref "LED12") (pin "4") (pinfunction "DIN_4") (pintype "passive"))
    )
    (net (code "26") (name "Net-(LED12-DOUT)") (class "Default")
      (node (ref "LED12") (pin "2") (pinfunction "DOUT_2") (pintype "passive"))
      (node (ref "LED13") (pin "4") (pinfunction "DIN_4") (pintype "passive"))
    )
    (net (code "27") (name "Net-(LED13-DOUT)") (class "Default")
      (node (ref "LED13") (pin "2") (pinfunction "DOUT_2") (pintype "passive"))
      (node (ref "LED14") (pin "4") (pinfunction "DIN_4") (pintype "passive"))
    )
    (net (code "28") (name "Net-(LED14-DOUT)") (class "Default")
      (node (ref "LED14") (pin "2") (pinfunction "DOUT_2") (pintype "passive"))
      (node (ref "LED16") (pin "4") (pinfunction "DIN_4") (pintype "passive"))
    )
    (net (code "29") (name "Net-(LED17-DOUT)") (class "Default")
      (node (ref "LED17") (pin "2") (pinfunction "DOUT_2") (pintype "passive"))
      (node (ref "LED18") (pin "4") (pinfunction "DIN_4") (pintype "passive"))
    )
    (net (code "30") (name "Net-(LED18-DOUT)") (class "Default")
      (node (ref "LED18") (pin "2") (pinfunction "DOUT_2") (pintype "passive"))
      (node (ref "LED19") (pin "4") (pinfunction "DIN_4") (pintype "passive"))
    )
    (net (code "31") (name "Net-(LED19-DOUT)") (class "Default")
      (node (ref "LED19") (pin "2") (pinfunction "DOUT_2") (pintype "passive"))
      (node (ref "LED21") (pin "4") (pinfunction "DIN_4") (pintype "passive"))
    )
    (net (code "32") (name "Net-(LED21-DOUT)") (class "Default")
      (node (ref "LED21") (pin "2") (pinfunction "DOUT_2") (pintype "passive"))
      (node (ref "LED22") (pin "4") (pinfunction "DIN_4") (pintype "passive"))
    )
    (net (code "33") (name "Net-(LED22-DOUT)") (class "Default")
      (node (ref "LED22") (pin "2") (pinfunction "DOUT_2") (pintype "passive"))
      (node (ref "LED23") (pin "4") (pinfunction "DIN_4") (pintype "passive"))
    )
    (net (code "34") (name "Net-(LED23-DOUT)") (class "Default")
      (node (ref "LED23") (pin "2") (pinfunction "DOUT_2") (pintype "passive"))
      (node (ref "LED24") (pin "4") (pinfunction "DIN_4") (pintype "passive"))
    )
    (net (code "35") (name "Net-(LED25-DOUT)") (class "Default")
      (node (ref "LED25") (pin "2") (pinfunction "DOUT_2") (pintype "passive"))
      (node (ref "LED27") (pin "4") (pinfunction "DIN_4") (pintype "passive"))
    )
    (net (code "36") (name "Net-(LED27-DOUT)") (class "Default")
      (node (ref "LED27") (pin "2") (pinfunction "DOUT_2") (pintype "passive"))
      (node (ref "LED28") (pin "4") (pinfunction "DIN_4") (pintype "passive"))
    )
    (net (code "37") (name "Net-(LED28-DOUT)") (class "Default")
      (node (ref "LED28") (pin "2") (pinfunction "DOUT_2") (pintype "passive"))
      (node (ref "LED29") (pin "4") (pinfunction "DIN_4") (pintype "passive"))
    )
    (net (code "38") (name "Net-(LED29-DOUT)") (class "Default")
      (node (ref "LED29") (pin "2") (pinfunction "DOUT_2") (pintype "passive"))
      (node (ref "LED30") (pin "4") (pinfunction "DIN_4") (pintype "passive"))
    )
    (net (code "39") (name "Net-(LED30-DOUT)") (class "Default")
      (node (ref "LED30") (pin "2") (pinfunction "DOUT_2") (pintype "passive"))
      (node (ref "LED32") (pin "4") (pinfunction "DIN_4") (pintype "passive"))
    )
    (net (code "40") (name "Net-(LED33-DOUT)") (class "Default")
      (node (ref "LED33") (pin "2") (pinfunction "DOUT_2") (pintype "passive"))
      (node (ref "LED34") (pin "4") (pinfunction "DIN_4") (pintype "passive"))
    )
    (net (code "41") (name "Net-(LED34-DOUT)") (class "Default")
      (node (ref "LED34") (pin "2") (pinfunction "DOUT_2") (pintype "passive"))
      (node (ref "LED35") (pin "4") (pinfunction "DIN_4") (pintype "passive"))
    )
    (net (code "42") (name "Net-(LED35-DOUT)") (class "Default")
      (node (ref "LED35") (pin "2") (pinfunction "DOUT_2") (pintype "passive"))
      (node (ref "LED36") (pin "4") (pinfunction "DIN_4") (pintype "passive"))
    )
    (net (code "43") (name "Net-(LED36-DOUT)") (class "Default")
      (node (ref "LED36") (pin "2") (pinfunction "DOUT_2") (pintype "passive"))
      (node (ref "LED37") (pin "4") (pinfunction "DIN_4") (pintype "passive"))
    )
    (net (code "44") (name "Net-(LED37-DOUT)") (class "Default")
      (node (ref "LED37") (pin "2") (pinfunction "DOUT_2") (pintype "passive"))
      (node (ref "LED39") (pin "4") (pinfunction "DIN_4") (pintype "passive"))
    )
    (net (code "45") (name "Net-(LED39-DOUT)") (class "Default")
      (node (ref "LED39") (pin "2") (pinfunction "DOUT_2") (pintype "passive"))
      (node (ref "LED40") (pin "4") (pinfunction "DIN_4") (pintype "passive"))
    )
    (net (code "46") (name "Net-(LED41-DOUT)") (class "Default")
      (node (ref "LED41") (pin "2") (pinfunction "DOUT_2") (pintype "passive"))
      (node (ref "LED42") (pin "4") (pinfunction "DIN_4") (pintype "passive"))
    )
    (net (code "47") (name "Net-(LED42-DOUT)") (class "Default")
      (node (ref "LED42") (pin "2") (pinfunction "DOUT_2") (pintype "passive"))
      (node (ref "LED44") (pin "4") (pinfunction "DIN_4") (pintype "passive"))
    )
    (net (code "48") (name "Net-(LED44-DOUT)") (class "Default")
      (node (ref "LED44") (pin "2") (pinfunction "DOUT_2") (pintype "passive"))
      (node (ref "LED45") (pin "4") (pinfunction "DIN_4") (pintype "passive"))
    )
    (net (code "49") (name "Net-(LED45-DOUT)") (class "Default")
      (node (ref "LED45") (pin "2") (pinfunction "DOUT_2") (pintype "passive"))
      (node (ref "LED46") (pin "4") (pinfunction "DIN_4") (pintype "passive"))
    )
    (net (code "50") (name "Net-(LED46-DOUT)") (class "Default")
      (node (ref "LED46") (pin "2") (pinfunction "DOUT_2") (pintype "passive"))
      (node (ref "LED47") (pin "4") (pinfunction "DIN_4") (pintype "passive"))
    )
    (net (code "51") (name "Net-(LED47-DOUT)") (class "Default")
      (node (ref "LED47") (pin "2") (pinfunction "DOUT_2") (pintype "passive"))
      (node (ref "LED48") (pin "4") (pinfunction "DIN_4") (pintype "passive"))
    )
    (net (code "52") (name "Net-(LED49-DOUT)") (class "Default")
      (node (ref "LED49") (pin "2") (pinfunction "DOUT_2") (pintype "passive"))
      (node (ref "LED51") (pin "4") (pinfunction "DIN_4") (pintype "passive"))
    )
    (net (code "53") (name "Net-(LED51-DOUT)") (class "Default")
      (node (ref "LED51") (pin "2") (pinfunction "DOUT_2") (pintype "passive"))
      (node (ref "LED52") (pin "4") (pinfunction "DIN_4") (pintype "passive"))
    )
    (net (code "54") (name "Net-(LED52-DOUT)") (class "Default")
      (node (ref "LED52") (pin "2") (pinfunction "DOUT_2") (pintype "passive"))
      (node (ref "LED53") (pin "4") (pinfunction "DIN_4") (pintype "passive"))
    )
    (net (code "55") (name "Net-(LED53-DOUT)") (class "Default")
      (node (ref "LED53") (pin "2") (pinfunction "DOUT_2") (pintype "passive"))
      (node (ref "LED54") (pin "4") (pinfunction "DIN_4") (pintype "passive"))
    )
    (net (code "56") (name "Net-(LED54-DOUT)") (class "Default")
      (node (ref "LED54") (pin "2") (pinfunction "DOUT_2") (pintype "passive"))
      (node (ref "LED56") (pin "4") (pinfunction "DIN_4") (pintype "passive"))
    )
    (net (code "57") (name "Net-(LED57-DOUT)") (class "Default")
      (node (ref "LED57") (pin "2") (pinfunction "DOUT_2") (pintype "passive"))
      (node (ref "LED58") (pin "4") (pinfunction "DIN_4") (pintype "passive"))
    )
    (net (code "58") (name "Net-(LED58-DOUT)") (class "Default")
      (node (ref "LED58") (pin "2") (pinfunction "DOUT_2") (pintype "passive"))
      (node (ref "LED59") (pin "4") (pinfunction "DIN_4") (pintype "passive"))
    )
    (net (code "59") (name "Net-(LED59-DOUT)") (class "Default")
      (node (ref "LED59") (pin "2") (pinfunction "DOUT_2") (pintype "passive"))
      (node (ref "LED60") (pin "4") (pinfunction "DIN_4") (pintype "passive"))
    )
    (net (code "60") (name "Net-(LED60-DOUT)") (class "Default")
      (node (ref "LED60") (pin "2") (pinfunction "DOUT_2") (pintype "passive"))
      (node (ref "LED61") (pin "4") (pinfunction "DIN_4") (pintype "passive"))
    )
    (net (code "61") (name "Net-(LED61-DOUT)") (class "Default")
      (node (ref "LED61") (pin "2") (pinfunction "DOUT_2") (pintype "passive"))
      (node (ref "LED63") (pin "4") (pinfunction "DIN_4") (pintype "passive"))
    )
    (net (code "62") (name "Net-(LED63-DOUT)") (class "Default")
      (node (ref "LED63") (pin "2") (pinfunction "DOUT_2") (pintype "passive"))
      (node (ref "LED64") (pin "4") (pinfunction "DIN_4") (pintype "passive"))
    )
    (net (code "63") (name "Net-(LED65-DOUT)") (class "Default")
      (node (ref "LED65") (pin "2") (pinfunction "DOUT_2") (pintype "passive"))
      (node (ref "LED66") (pin "4") (pinfunction "DIN_4") (pintype "passive"))
    )
    (net (code "64") (name "Net-(LED66-DOUT)") (class "Default")
      (node (ref "LED66") (pin "2") (pinfunction "DOUT_2") (pintype "passive"))
      (node (ref "LED68") (pin "4") (pinfunction "DIN_4") (pintype "passive"))
    )
    (net (code "65") (name "Net-(LED68-DOUT)") (class "Default")
      (node (ref "LED68") (pin "2") (pinfunction "DOUT_2") (pintype "passive"))
      (node (ref "LED69") (pin "4") (pinfunction "DIN_4") (pintype "passive"))
    )
    (net (code "66") (name "Net-(LED69-DOUT)") (class "Default")
      (node (ref "LED69") (pin "2") (pinfunction "DOUT_2") (pintype "passive"))
      (node (ref "LED70") (pin "4") (pinfunction "DIN_4") (pintype "passive"))
    )
    (net (code "67") (name "Net-(LED70-DOUT)") (class "Default")
      (node (ref "LED70") (pin "2") (pinfunction "DOUT_2") (pintype "passive"))
      (node (ref "LED71") (pin "4") (pinfunction "DIN_4") (pintype "passive"))
    )
    (net (code "68") (name "Net-(LED71-DOUT)") (class "Default")
      (node (ref "LED71") (pin "2") (pinfunction "DOUT_2") (pintype "passive"))
      (node (ref "LED72") (pin "4") (pinfunction "DIN_4") (pintype "passive"))
    )
    (net (code "69") (name "Net-(LED74-DOUT)") (class "Default")
      (node (ref "LED74") (pin "2") (pinfunction "DOUT_2") (pintype "passive"))
      (node (ref "LED75") (pin "4") (pinfunction "DIN_4") (pintype "passive"))
    )
    (net (code "70") (name "Net-(LED75-DOUT)") (class "Default")
      (node (ref "LED75") (pin "2") (pinfunction "DOUT_2") (pintype "passive"))
      (node (ref "LED76") (pin "4") (pinfunction "DIN_4") (pintype "passive"))
    )
    (net (code "71") (name "Net-(LED76-DOUT)") (class "Default")
      (node (ref "LED76") (pin "2") (pinfunction "DOUT_2") (pintype "passive"))
      (node (ref "LED77") (pin "4") (pinfunction "DIN_4") (pintype "passive"))
    )
    (net (code "72") (name "Net-(LED77-DOUT)") (class "Default")
      (node (ref "LED77") (pin "2") (pinfunction "DOUT_2") (pintype "passive"))
      (node (ref "LED79") (pin "4") (pinfunction "DIN_4") (pintype "passive"))
    )
    (net (code "73") (name "Net-(LED79-DOUT)") (class "Default")
      (node (ref "LED79") (pin "2") (pinfunction "DOUT_2") (pintype "passive"))
      (node (ref "LED80") (pin "4") (pinfunction "DIN_4") (pintype "passive"))
    )
    (net (code "74") (name "Net-(LED81-DOUT)") (class "Default")
      (node (ref "LED81") (pin "2") (pinfunction "DOUT_2") (pintype "passive"))
      (node (ref "LED83") (pin "4") (pinfunction "DIN_4") (pintype "passive"))
    )
    (net (code "75") (name "Net-(LED83-DOUT)") (class "Default")
      (node (ref "LED83") (pin "2") (pinfunction "DOUT_2") (pintype "passive"))
      (node (ref "LED84") (pin "4") (pinfunction "DIN_4") (pintype "passive"))
    )
    (net (code "76") (name "Net-(LED84-DOUT)") (class "Default")
      (node (ref "LED84") (pin "2") (pinfunction "DOUT_2") (pintype "passive"))
      (node (ref "LED85") (pin "4") (pinfunction "DIN_4") (pintype "passive"))
    )
    (net (code "77") (name "Net-(LED85-DOUT)") (class "Default")
      (node (ref "LED85") (pin "2") (pinfunction "DOUT_2") (pintype "passive"))
      (node (ref "LED86") (pin "4") (pinfunction "DIN_4") (pintype "passive"))
    )
    (net (code "78") (name "Net-(LED86-DOUT)") (class "Default")
      (node (ref "LED86") (pin "2") (pinfunction "DOUT_2") (pintype "passive"))
      (node (ref "LED88") (pin "4") (pinfunction "DIN_4") (pintype "passive"))
    )
    (net (code "79") (name "Net-(LED89-DOUT)") (class "Default")
      (node (ref "LED89") (pin "2") (pinfunction "DOUT_2") (pintype "passive"))
      (node (ref "LED90") (pin "4") (pinfunction "DIN_4") (pintype "passive"))
    )
    (net (code "80") (name "Net-(LED90-DOUT)") (class "Default")
      (node (ref "LED90") (pin "2") (pinfunction "DOUT_2") (pintype "passive"))
      (node (ref "LED91") (pin "4") (pinfunction "DIN_4") (pintype "passive"))
    )
    (net (code "81") (name "Net-(LED91-DOUT)") (class "Default")
      (node (ref "LED91") (pin "2") (pinfunction "DOUT_2") (pintype "passive"))
      (node (ref "LED92") (pin "4") (pinfunction "DIN_4") (pintype "passive"))
    )
  )
)
